# ssd1306-i2c-oled-breakout.net
KiCad netlist of a schematic drawn in EAGLE
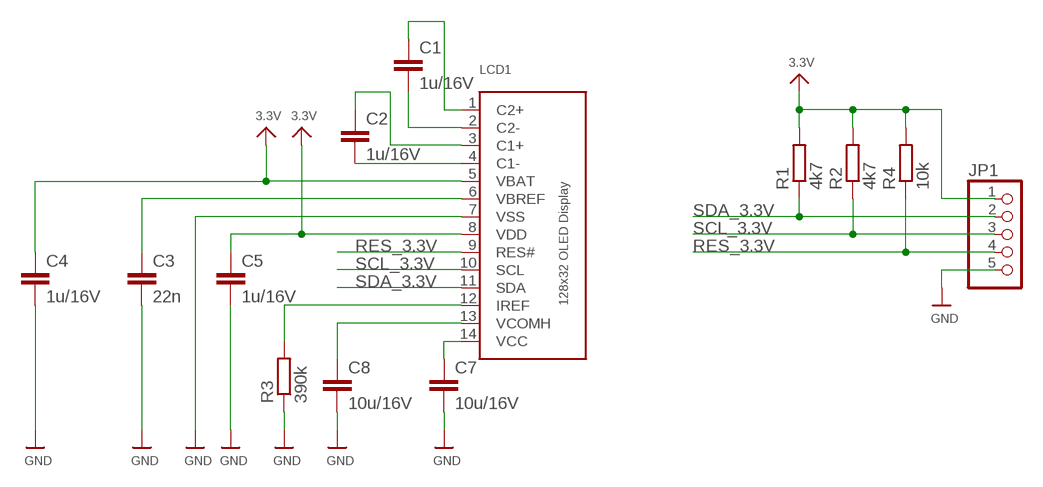
[diagram p0: schematic, sheet 1]

(export (version "E")
  (design (tool "Eeschema 10.0.6"))
  (components
    (comp (ref "C1")
      (value "1u/16V")
      (footprint "eagle-import:C0603")
      (libsource (lib "eagle-import") (part "C-EUC0603"))
    )
    (comp (ref "C2")
      (value "1u/16V")
      (footprint "eagle-import:C0603")
      (libsource (lib "eagle-import") (part "C-EUC0603"))
    )
    (comp (ref "C3")
      (value "22n")
      (footprint "eagle-import:C0603")
      (libsource (lib "eagle-import") (part "C-EUC0603"))
    )
    (comp (ref "C4")
      (value "1u/16V")
      (footprint "eagle-import:C0603")
      (libsource (lib "eagle-import") (part "C-EUC0603"))
    )
    (comp (ref "C5")
      (value "1u/16V")
      (footprint "eagle-import:C0603")
      (libsource (lib "eagle-import") (part "C-EUC0603"))
    )
    (comp (ref "C7")
      (value "10u/16V")
      (footprint "eagle-import:C0805")
      (libsource (lib "eagle-import") (part "C-EUC0805"))
    )
    (comp (ref "C8")
      (value "10u/16V")
      (footprint "eagle-import:C0805")
      (libsource (lib "eagle-import") (part "C-EUC0805"))
    )
    (comp (ref "JP1")
      (value "PINHD-1X5")
      (footprint "eagle-import:1X05")
      (libsource (lib "eagle-import") (part "PINHD-1X5"))
    )
    (comp (ref "LCD1")
      (value "DISP_OLED_UG-2832HSWEG02")
      (footprint "eagle-import:UG-2832HSWEG02_WRAPUNDER")
      (libsource (lib "eagle-import") (part "DISP_OLED_UG-2832HSWEG02"))
    )
    (comp (ref "R1")
      (value "4k7")
      (footprint "eagle-import:R0805")
      (libsource (lib "eagle-import") (part "R-EU_R0805"))
    )
    (comp (ref "R2")
      (value "4k7")
      (footprint "eagle-import:R0805")
      (libsource (lib "eagle-import") (part "R-EU_R0805"))
    )
    (comp (ref "R3")
      (value "390k")
      (footprint "eagle-import:R0603")
      (libsource (lib "eagle-import") (part "R-EU_R0603"))
    )
    (comp (ref "R4")
      (value "10k")
      (footprint "eagle-import:R0805")
      (libsource (lib "eagle-import") (part "R-EU_R0805"))
    )
  )
  (nets
    (net (code "1") (name "/RES_3.3V") (class "Default")
      (node (ref "JP1") (pin "4") (pinfunction "4_4") (pintype "passive"))
      (node (ref "LCD1") (pin "9") (pinfunction "RES#_9") (pintype "bidirectional"))
      (node (ref "R4") (pin "1") (pinfunction "1_1") (pintype "passive"))
    )
    (net (code "2") (name "/SCL_3.3V") (class "Default")
      (node (ref "JP1") (pin "3") (pinfunction "3_3") (pintype "passive"))
      (node (ref "LCD1") (pin "10") (pinfunction "SCL_10") (pintype "bidirectional"))
      (node (ref "R2") (pin "1") (pinfunction "1_1") (pintype "passive"))
    )
    (net (code "3") (name "/SDA_3.3V") (class "Default")
      (node (ref "JP1") (pin "2") (pinfunction "2_2") (pintype "passive"))
      (node (ref "LCD1") (pin "11") (pinfunction "SDA_11") (pintype "bidirectional"))
      (node (ref "R1") (pin "1") (pinfunction "1_1") (pintype "passive"))
    )
    (net (code "4") (name "3.3V") (class "Default")
      (node (ref "C4") (pin "1") (pinfunction "1_1") (pintype "passive"))
      (node (ref "C5") (pin "1") (pinfunction "1_1") (pintype "passive"))
      (node (ref "JP1") (pin "1") (pinfunction "1_1") (pintype "passive"))
      (node (ref "LCD1") (pin "5") (pinfunction "VBAT_5") (pintype "power_in"))
      (node (ref "LCD1") (pin "8") (pinfunction "VDD_8") (pintype "power_in"))
      (node (ref "R1") (pin "2") (pinfunction "2_2") (pintype "passive"))
      (node (ref "R2") (pin "2") (pinfunction "2_2") (pintype "passive"))
      (node (ref "R4") (pin "2") (pinfunction "2_2") (pintype "passive"))
    )
    (net (code "5") (name "GND") (class "Default")
      (node (ref "C3") (pin "2") (pinfunction "2_2") (pintype "passive"))
      (node (ref "C4") (pin "2") (pinfunction "2_2") (pintype "passive"))
      (node (ref "C5") (pin "2") (pinfunction "2_2") (pintype "passive"))
      (node (ref "C7") (pin "2") (pinfunction "2_2") (pintype "passive"))
      (node (ref "C8") (pin "2") (pinfunction "2_2") (pintype "passive"))
      (node (ref "JP1") (pin "5") (pinfunction "5_5") (pintype "passive"))
      (node (ref "LCD1") (pin "7") (pinfunction "VSS_7") (pintype "power_in"))
      (node (ref "R3") (pin "1") (pinfunction "1_1") (pintype "passive"))
    )
    (net (code "6") (name "Net-(LCD1-C1+)") (class "Default")
      (node (ref "C2") (pin "1") (pinfunction "1_1") (pintype "passive"))
      (node (ref "LCD1") (pin "3") (pinfunction "C1+_3") (pintype "bidirectional"))
    )
    (net (code "7") (name "Net-(LCD1-C1-)") (class "Default")
      (node (ref "C2") (pin "2") (pinfunction "2_2") (pintype "passive"))
      (node (ref "LCD1") (pin "4") (pinfunction "C1-_4") (pintype "bidirectional"))
    )
    (net (code "8") (name "Net-(LCD1-C2+)") (class "Default")
      (node (ref "C1") (pin "1") (pinfunction "1_1") (pintype "passive"))
      (node (ref "LCD1") (pin "1") (pinfunction "C2+_1") (pintype "bidirectional"))
    )
    (net (code "9") (name "Net-(LCD1-C2-)") (class "Default")
      (node (ref "C1") (pin "2") (pinfunction "2_2") (pintype "passive"))
      (node (ref "LCD1") (pin "2") (pinfunction "C2-_2") (pintype "bidirectional"))
    )
    (net (code "10") (name "Net-(LCD1-IREF)") (class "Default")
      (node (ref "LCD1") (pin "12") (pinfunction "IREF_12") (pintype "bidirectional"))
      (node (ref "R3") (pin "2") (pinfunction "2_2") (pintype "passive"))
    )
    (net (code "11") (name "Net-(LCD1-VBREF)") (class "Default")
      (node (ref "C3") (pin "1") (pinfunction "1_1") (pintype "passive"))
      (node (ref "LCD1") (pin "6") (pinfunction "VBREF_6") (pintype "power_in"))
    )
    (net (code "12") (name "Net-(LCD1-VCC)") (class "Default")
      (node (ref "C7") (pin "1") (pinfunction "1_1") (pintype "passive"))
      (node (ref "LCD1") (pin "14") (pinfunction "VCC_14") (pintype "power_in"))
    )
    (net (code "13") (name "Net-(LCD1-VCOMH)") (class "Default")
      (node (ref "C8") (pin "1") (pinfunction "1_1") (pintype "passive"))
      (node (ref "LCD1") (pin "13") (pinfunction "VCOMH_13") (pintype "power_in"))
    )
  )
)
